# 05_3V3_GENERATION.net
KiCad netlist of a schematic drawn in Altium Designer
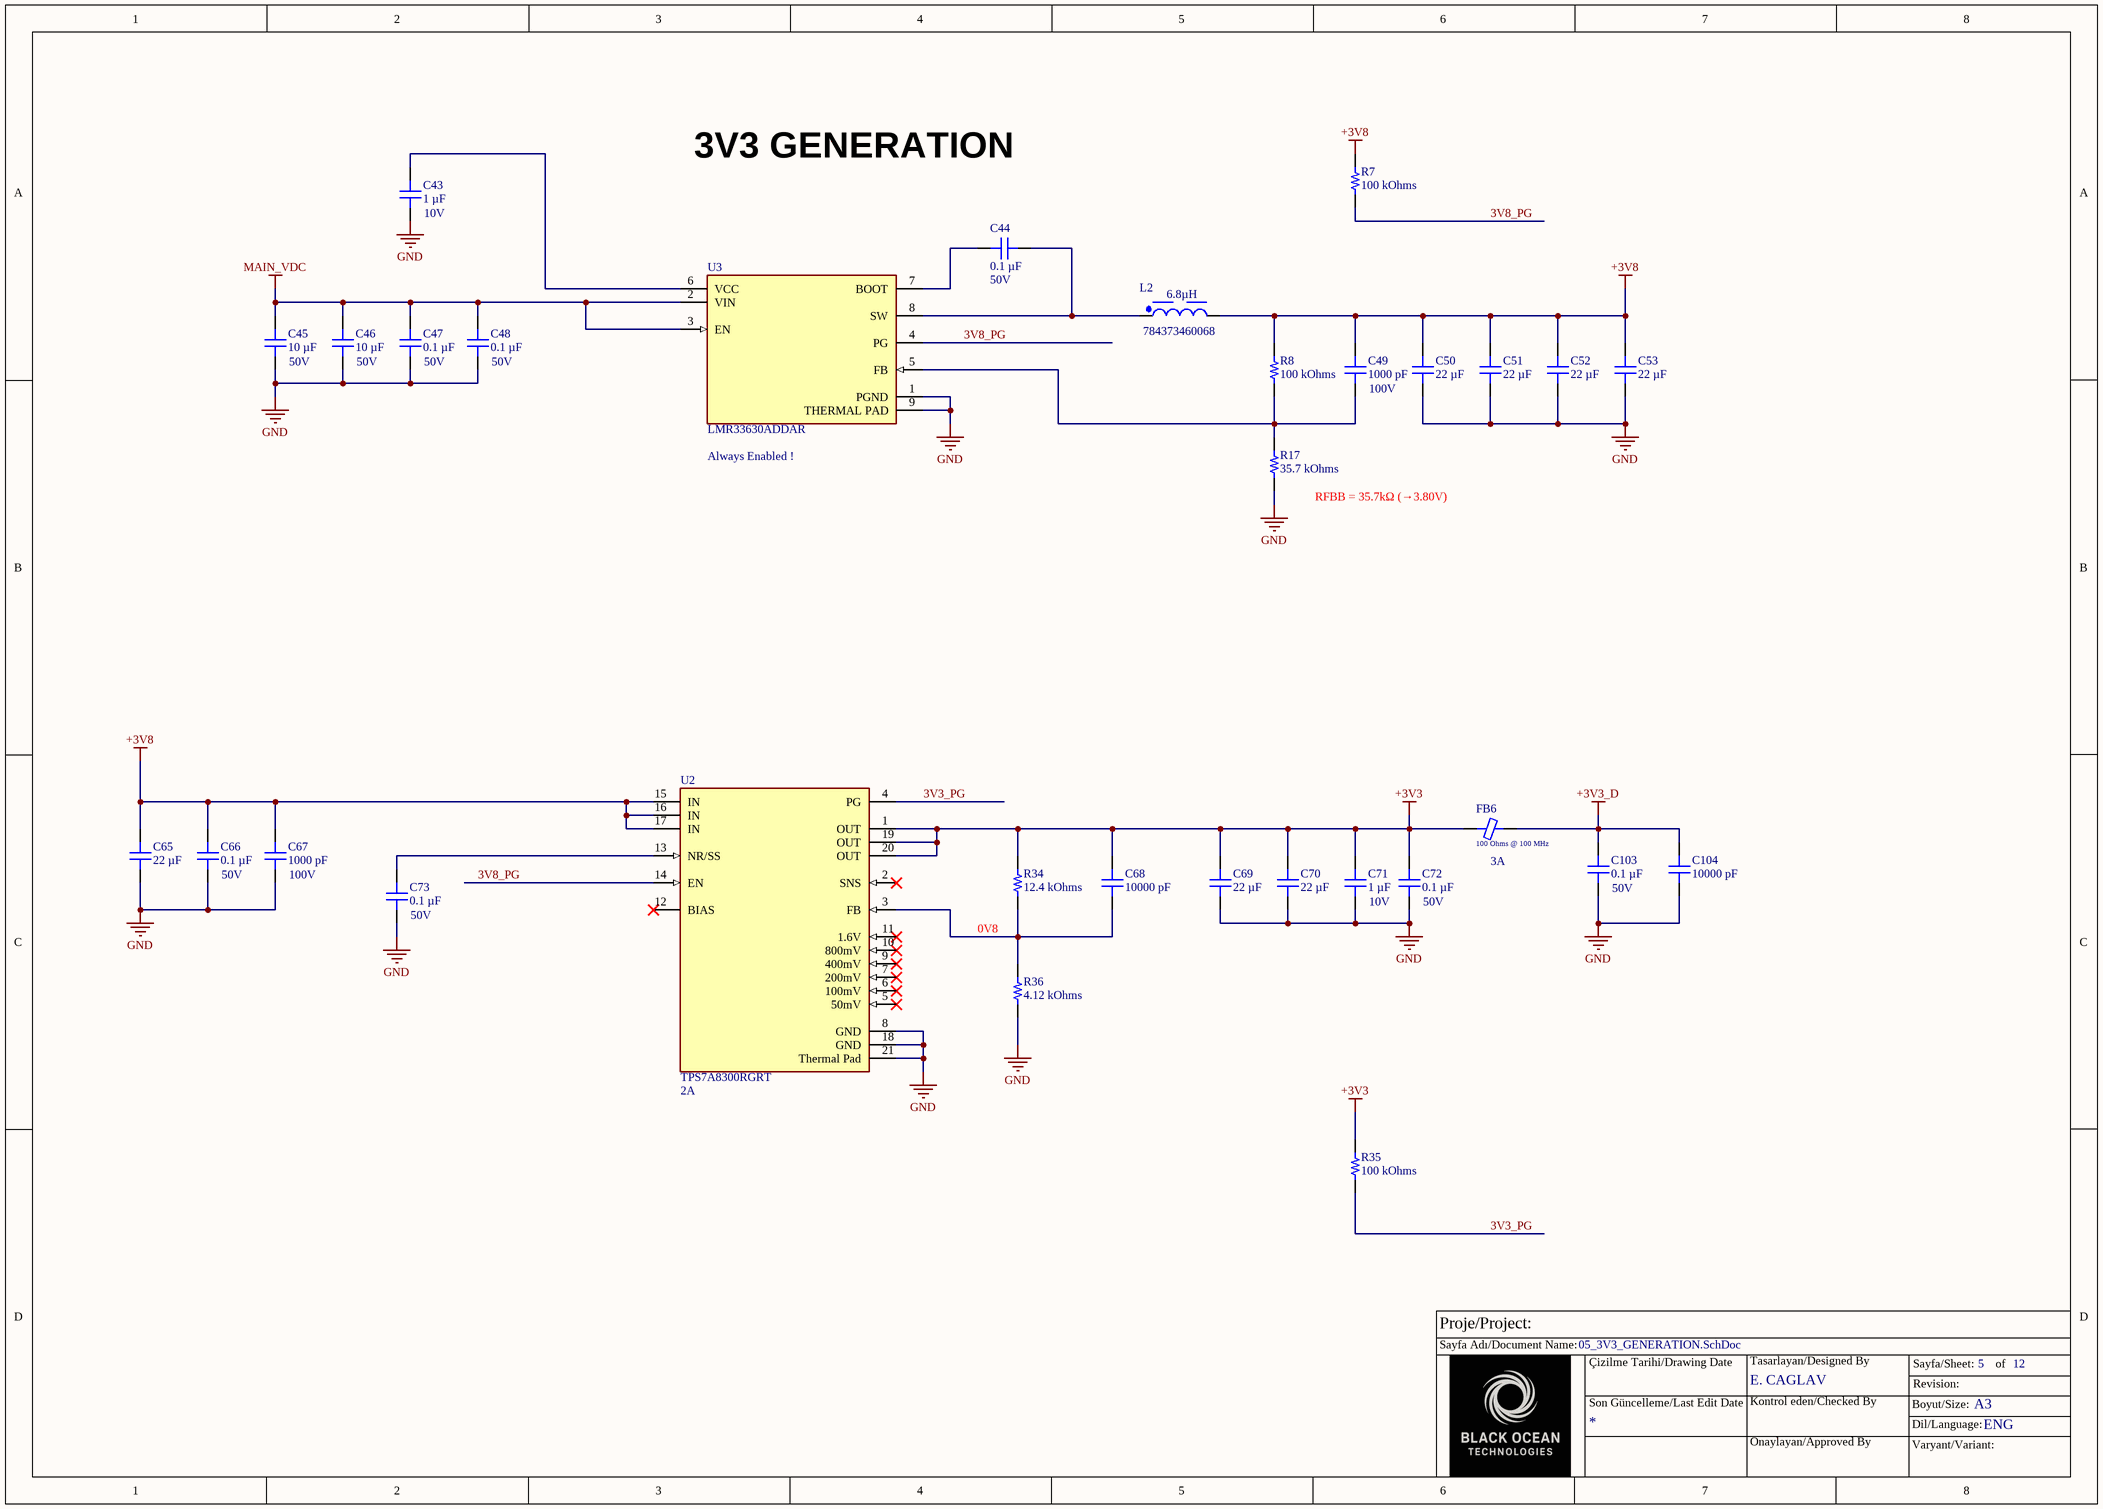
[diagram p0: 05_3V3_GENERATION.SchDoc]

(export (version "E")
  (design (tool "Eeschema 10.0.6"))
  (components
    (comp (ref "C43")
      (value "1 µF")
      (footprint "CAP 0402_1005")
      (description "CAP CER 1UF 10V X7S 0402")
      (fields
        (field (name "PART NUMBER") "GRM155C71A105KE11D")
        (field (name "CAPACITANCE") "1 µF")
        (field (name "MANUFACTURER") "Murata Electronics")
        (field (name "VOLTAGE - RATED") "10V")
      )
      (libsource (lib "Celestial Altium Library - altium_library") (part "Capacitor"))
    )
    (comp (ref "C44")
      (value "0.1 µF")
      (footprint "CAP 0402_1005")
      (description "CAP CER 0.1UF 50V X7R 0402")
      (fields
        (field (name "PART NUMBER") "GCM155R71H104KE02J")
        (field (name "CAPACITANCE") "0.1 µF")
        (field (name "MANUFACTURER") "Murata Electronics")
        (field (name "VOLTAGE - RATED") "50V")
      )
      (libsource (lib "Celestial Altium Library - altium_library") (part "Capacitor"))
    )
    (comp (ref "C45")
      (value "10 µF")
      (footprint "CAP 1206_3216 - 0.8MM")
      (description "CAP CER 10UF 50V X7R 1206")
      (fields
        (field (name "PART NUMBER") "CL31B106KBHNNNE")
        (field (name "CAPACITANCE") "10 µF")
        (field (name "MANUFACTURER") "Samsung Electro-Mechanics")
        (field (name "VOLTAGE - RATED") "50V")
      )
      (libsource (lib "Celestial Altium Library - altium_library") (part "Capacitor"))
    )
    (comp (ref "C46")
      (value "10 µF")
      (footprint "CAP 1206_3216 - 0.8MM")
      (description "CAP CER 10UF 50V X7R 1206")
      (fields
        (field (name "PART NUMBER") "CL31B106KBHNNNE")
        (field (name "CAPACITANCE") "10 µF")
        (field (name "MANUFACTURER") "Samsung Electro-Mechanics")
        (field (name "VOLTAGE - RATED") "50V")
      )
      (libsource (lib "Celestial Altium Library - altium_library") (part "Capacitor"))
    )
    (comp (ref "C47")
      (value "0.1 µF")
      (footprint "CAP 0402_1005")
      (description "CAP CER 0.1UF 50V X7R 0402")
      (fields
        (field (name "PART NUMBER") "GCM155R71H104KE02J")
        (field (name "CAPACITANCE") "0.1 µF")
        (field (name "MANUFACTURER") "Murata Electronics")
        (field (name "VOLTAGE - RATED") "50V")
      )
      (libsource (lib "Celestial Altium Library - altium_library") (part "Capacitor"))
    )
    (comp (ref "C48")
      (value "0.1 µF")
      (footprint "CAP 0402_1005")
      (description "CAP CER 0.1UF 50V X7R 0402")
      (fields
        (field (name "PART NUMBER") "GCM155R71H104KE02J")
        (field (name "CAPACITANCE") "0.1 µF")
        (field (name "MANUFACTURER") "Murata Electronics")
        (field (name "VOLTAGE - RATED") "50V")
      )
      (libsource (lib "Celestial Altium Library - altium_library") (part "Capacitor"))
    )
    (comp (ref "C49")
      (value "1000 pF")
      (footprint "CAP 0402_1005")
      (description "CAP CER 1000PF 100V C0G/NP0 0402")
      (fields
        (field (name "PART NUMBER") "C0402H102J1GAC7867")
        (field (name "CAPACITANCE") "1000 pF")
        (field (name "MANUFACTURER") "KEMET")
        (field (name "VOLTAGE - RATED") "100V")
      )
      (libsource (lib "Celestial Altium Library - altium_library") (part "Capacitor"))
    )
    (comp (ref "C50")
      (value "22 µF")
      (footprint "CAP 0805_2012")
      (description "CAP CER 22UF 16V X5R 0805")
      (fields
        (field (name "PART NUMBER") "CL21A226KOQNNNE")
        (field (name "CAPACITANCE") "22 µF")
        (field (name "MANUFACTURER") "Samsung Electro-Mechanics")
      )
      (libsource (lib "Celestial Altium Library - altium_library") (part "Capacitor"))
    )
    (comp (ref "C51")
      (value "22 µF")
      (footprint "CAP 0805_2012")
      (description "CAP CER 22UF 16V X5R 0805")
      (fields
        (field (name "PART NUMBER") "CL21A226KOQNNNE")
        (field (name "CAPACITANCE") "22 µF")
        (field (name "MANUFACTURER") "Samsung Electro-Mechanics")
      )
      (libsource (lib "Celestial Altium Library - altium_library") (part "Capacitor"))
    )
    (comp (ref "C52")
      (value "22 µF")
      (footprint "CAP 0805_2012")
      (description "CAP CER 22UF 16V X5R 0805")
      (fields
        (field (name "PART NUMBER") "CL21A226KOQNNNE")
        (field (name "CAPACITANCE") "22 µF")
        (field (name "MANUFACTURER") "Samsung Electro-Mechanics")
      )
      (libsource (lib "Celestial Altium Library - altium_library") (part "Capacitor"))
    )
    (comp (ref "C53")
      (value "22 µF")
      (footprint "CAP 0805_2012")
      (description "CAP CER 22UF 16V X5R 0805")
      (fields
        (field (name "PART NUMBER") "CL21A226KOQNNNE")
        (field (name "CAPACITANCE") "22 µF")
        (field (name "MANUFACTURER") "Samsung Electro-Mechanics")
      )
      (libsource (lib "Celestial Altium Library - altium_library") (part "Capacitor"))
    )
    (comp (ref "C65")
      (value "22 µF")
      (footprint "CAP 0805_2012")
      (description "CAP CER 22UF 16V X5R 0805")
      (fields
        (field (name "PART NUMBER") "CL21A226KOQNNNE")
        (field (name "CAPACITANCE") "22 µF")
        (field (name "MANUFACTURER") "Samsung Electro-Mechanics")
      )
      (libsource (lib "Celestial Altium Library - altium_library") (part "Capacitor"))
    )
    (comp (ref "C66")
      (value "0.1 µF")
      (footprint "CAP 0402_1005")
      (description "CAP CER 0.1UF 50V X7R 0402")
      (fields
        (field (name "PART NUMBER") "GCM155R71H104KE02J")
        (field (name "CAPACITANCE") "0.1 µF")
        (field (name "MANUFACTURER") "Murata Electronics")
        (field (name "VOLTAGE - RATED") "50V")
      )
      (libsource (lib "Celestial Altium Library - altium_library") (part "Capacitor"))
    )
    (comp (ref "C67")
      (value "1000 pF")
      (footprint "CAP 0402_1005")
      (description "CAP CER 1000PF 100V C0G/NP0 0402")
      (fields
        (field (name "PART NUMBER") "C0402H102J1GAC7867")
        (field (name "CAPACITANCE") "1000 pF")
        (field (name "MANUFACTURER") "KEMET")
        (field (name "VOLTAGE - RATED") "100V")
      )
      (libsource (lib "Celestial Altium Library - altium_library") (part "Capacitor"))
    )
    (comp (ref "C68")
      (value "10000 pF")
      (footprint "CAP 0402_1005")
      (description "CAP CER 10000PF 50V X7R 0402")
      (fields
        (field (name "PART NUMBER") "AC0402KPX7R9BB103")
        (field (name "CAPACITANCE") "10000 pF")
        (field (name "MANUFACTURER") "Yageo")
      )
      (libsource (lib "Celestial Altium Library - altium_library") (part "Capacitor"))
    )
    (comp (ref "C69")
      (value "22 µF")
      (footprint "CAP 0805_2012")
      (description "CAP CER 22UF 16V X5R 0805")
      (fields
        (field (name "PART NUMBER") "CL21A226KOQNNNE")
        (field (name "CAPACITANCE") "22 µF")
        (field (name "MANUFACTURER") "Samsung Electro-Mechanics")
      )
      (libsource (lib "Celestial Altium Library - altium_library") (part "Capacitor"))
    )
    (comp (ref "C70")
      (value "22 µF")
      (footprint "CAP 0805_2012")
      (description "CAP CER 22UF 16V X5R 0805")
      (fields
        (field (name "PART NUMBER") "CL21A226KOQNNNE")
        (field (name "CAPACITANCE") "22 µF")
        (field (name "MANUFACTURER") "Samsung Electro-Mechanics")
      )
      (libsource (lib "Celestial Altium Library - altium_library") (part "Capacitor"))
    )
    (comp (ref "C71")
      (value "1 µF")
      (footprint "CAP 0402_1005")
      (description "CAP CER 1UF 10V X7S 0402")
      (fields
        (field (name "PART NUMBER") "GRM155C71A105KE11D")
        (field (name "CAPACITANCE") "1 µF")
        (field (name "MANUFACTURER") "Murata Electronics")
        (field (name "VOLTAGE - RATED") "10V")
      )
      (libsource (lib "Celestial Altium Library - altium_library") (part "Capacitor"))
    )
    (comp (ref "C72")
      (value "0.1 µF")
      (footprint "CAP 0402_1005")
      (description "CAP CER 0.1UF 50V X7R 0402")
      (fields
        (field (name "PART NUMBER") "GCM155R71H104KE02J")
        (field (name "CAPACITANCE") "0.1 µF")
        (field (name "MANUFACTURER") "Murata Electronics")
        (field (name "VOLTAGE - RATED") "50V")
      )
      (libsource (lib "Celestial Altium Library - altium_library") (part "Capacitor"))
    )
    (comp (ref "C73")
      (value "0.1 µF")
      (footprint "CAP 0402_1005")
      (description "CAP CER 0.1UF 50V X7R 0402")
      (fields
        (field (name "PART NUMBER") "GCM155R71H104KE02J")
        (field (name "CAPACITANCE") "0.1 µF")
        (field (name "MANUFACTURER") "Murata Electronics")
        (field (name "VOLTAGE - RATED") "50V")
      )
      (libsource (lib "Celestial Altium Library - altium_library") (part "Capacitor"))
    )
    (comp (ref "C103")
      (value "0.1 µF")
      (footprint "CAP 0402_1005")
      (description "CAP CER 0.1UF 50V X7R 0402")
      (fields
        (field (name "PART NUMBER") "GCM155R71H104KE02J")
        (field (name "CAPACITANCE") "0.1 µF")
        (field (name "MANUFACTURER") "Murata Electronics")
        (field (name "VOLTAGE - RATED") "50V")
      )
      (libsource (lib "Celestial Altium Library - altium_library") (part "Capacitor"))
    )
    (comp (ref "C104")
      (value "10000 pF")
      (footprint "CAP 0402_1005")
      (description "CAP CER 10000PF 50V X7R 0402")
      (fields
        (field (name "PART NUMBER") "AC0402KPX7R9BB103")
        (field (name "CAPACITANCE") "10000 pF")
        (field (name "MANUFACTURER") "Yageo")
      )
      (libsource (lib "Celestial Altium Library - altium_library") (part "Capacitor"))
    )
    (comp (ref "FB6")
      (value "100 Ohms @ 100 MHz")
      (footprint "FER 0603_1608")
      (description "FERRITE BEAD 100 OHM 0603 1LN")
      (fields
        (field (name "PART NUMBER") "MH1608-101Y")
        (field (name "CURRENT RATING (MAX)") "3A")
        (field (name "MANUFACTURER") "Bourns Inc.")
      )
      (libsource (lib "Celestial Altium Library - altium_library") (part "Ferrite Chip"))
    )
    (comp (ref "L2")
      (value "784373460068")
      (footprint "WE-LHCA_7030")
      (description "Power Inductor, 6.8UH, 4.5A, Shielded Rohs Compliant: Yes")
      (fields (field (name "INDUCTANCE") "6.8µH"))
      (libsource (lib "Altium Content Vault") (part "Inductor - 2"))
    )
    (comp (ref "R7")
      (value "100 kOhms")
      (footprint "RES 0402_1005")
      (description "RES SMD 100K OHM 1% 1/16W 0402")
      (fields (field (name "PART NUMBER") "AC0402FR-07100KL") (field (name "MANUFACTURER") "Yageo"))
      (libsource (lib "Celestial Altium Library - altium_library") (part "Resistor"))
    )
    (comp (ref "R8")
      (value "100 kOhms")
      (footprint "RES 0402_1005")
      (description "RES 100K OHM 1% 1/16W 0402")
      (fields (field (name "PART NUMBER") "RC0402FR-13100KL") (field (name "MANUFACTURER") "Yageo"))
      (libsource (lib "Celestial Altium Library - altium_library") (part "Resistor"))
    )
    (comp (ref "R17")
      (value "35.7 kOhms")
      (footprint "RES 0402_1005")
      (description "RES SMD 35.7KOHM 0.1% 1/16W 0402")
      (fields
        (field (name "PART NUMBER") "ERA-2AEB3572X")
        (field (name "MANUFACTURER") "Panasonic Electronic Components")
      )
      (libsource (lib "Celestial Altium Library - altium_library") (part "Resistor"))
    )
    (comp (ref "R34")
      (value "12.4 kOhms")
      (footprint "RES 0402_1005")
      (description "RES SMD 12.4K OHM 1% 1/16W 0402")
      (fields (field (name "PART NUMBER") "AC0402FR-0712K4L") (field (name "MANUFACTURER") "Yageo"))
      (libsource (lib "Celestial Altium Library - altium_library") (part "Resistor"))
    )
    (comp (ref "R35")
      (value "100 kOhms")
      (footprint "RES 0402_1005")
      (description "RES SMD 100K OHM 1% 1/16W 0402")
      (fields (field (name "PART NUMBER") "AC0402FR-07100KL") (field (name "MANUFACTURER") "Yageo"))
      (libsource (lib "Celestial Altium Library - altium_library") (part "Resistor"))
    )
    (comp (ref "R36")
      (value "4.12 kOhms")
      (footprint "RES 0402_1005")
      (description "RES SMD 4.12KOHM 0.1% 1/16W 0402")
      (fields
        (field (name "PART NUMBER") "ERA-2AEB4121X")
        (field (name "MANUFACTURER") "Panasonic Electronic Components")
      )
      (libsource (lib "Celestial Altium Library - altium_library") (part "Resistor"))
    )
    (comp (ref "U2")
      (value "TPS7A8300RGRT")
      (footprint "FP-RGR0020A-MFG")
      (description "IC REG LINEAR POS ADJ 2A 20VQFN")
      (fields (field (name "OUTPUT CURRENT") "2A"))
      (libsource (lib "Altium Content Vault") (part "693c5293fa25e994f17fd2590bf4031"))
    )
    (comp (ref "U3")
      (value "LMR33630ADDAR")
      (footprint "FP-DDA0008J-MFG")
      (description "IC REG BUCK ADJUSTABLE 3A 8SOPWR")
      (libsource (lib "Altium Content Vault") (part "6a354f5098e7f60ae670b755afcc2ec"))
    )
  )
  (nets
    (net (code "1") (name "+3V3") (class "Default")
      (node (ref "C68") (pin "2") (pinfunction "2_2") (pintype "passive"))
      (node (ref "C69") (pin "2") (pinfunction "2_2") (pintype "passive"))
      (node (ref "C70") (pin "2") (pinfunction "2_2") (pintype "passive"))
      (node (ref "C71") (pin "1") (pinfunction "1_1") (pintype "passive"))
      (node (ref "C72") (pin "2") (pinfunction "2_2") (pintype "passive"))
      (node (ref "FB6") (pin "2") (pinfunction "2_2") (pintype "passive"))
      (node (ref "R34") (pin "2") (pinfunction "2_2") (pintype "passive"))
      (node (ref "R35") (pin "2") (pinfunction "2_2") (pintype "passive"))
      (node (ref "U2") (pin "1") (pinfunction "OUT_1") (pintype "passive"))
      (node (ref "U2") (pin "19") (pinfunction "OUT_19") (pintype "passive"))
      (node (ref "U2") (pin "20") (pinfunction "OUT_20") (pintype "passive"))
    )
    (net (code "2") (name "+3V3_D") (class "Default")
      (node (ref "C103") (pin "2") (pinfunction "2_2") (pintype "passive"))
      (node (ref "C104") (pin "2") (pinfunction "2_2") (pintype "passive"))
      (node (ref "FB6") (pin "1") (pinfunction "1_1") (pintype "passive"))
    )
    (net (code "3") (name "+3V8") (class "Default")
      (node (ref "C49") (pin "2") (pinfunction "2_2") (pintype "passive"))
      (node (ref "C50") (pin "2") (pinfunction "2_2") (pintype "passive"))
      (node (ref "C51") (pin "2") (pinfunction "2_2") (pintype "passive"))
      (node (ref "C52") (pin "2") (pinfunction "2_2") (pintype "passive"))
      (node (ref "C53") (pin "2") (pinfunction "2_2") (pintype "passive"))
      (node (ref "C65") (pin "2") (pinfunction "2_2") (pintype "passive"))
      (node (ref "C66") (pin "2") (pinfunction "2_2") (pintype "passive"))
      (node (ref "C67") (pin "2") (pinfunction "2_2") (pintype "passive"))
      (node (ref "L2") (pin "2") (pinfunction "2_2") (pintype "passive"))
      (node (ref "R7") (pin "2") (pinfunction "2_2") (pintype "passive"))
      (node (ref "R8") (pin "2") (pinfunction "2_2") (pintype "passive"))
      (node (ref "U2") (pin "15") (pinfunction "IN_15") (pintype "power_in"))
      (node (ref "U2") (pin "16") (pinfunction "IN_16") (pintype "power_in"))
      (node (ref "U2") (pin "17") (pinfunction "IN_17") (pintype "power_in"))
    )
    (net (code "4") (name "/3V3_PG") (class "Default")
      (node (ref "R35") (pin "1") (pinfunction "1_1") (pintype "passive"))
      (node (ref "U2") (pin "4") (pinfunction "PG_4") (pintype "open_collector"))
    )
    (net (code "5") (name "/3V8_PG") (class "Default")
      (node (ref "R7") (pin "1") (pinfunction "1_1") (pintype "passive"))
      (node (ref "U2") (pin "14") (pinfunction "EN_14") (pintype "input"))
      (node (ref "U3") (pin "4") (pinfunction "PG_4") (pintype "open_collector"))
    )
    (net (code "6") (name "GND") (class "Default")
      (node (ref "C103") (pin "1") (pinfunction "1_1") (pintype "passive"))
      (node (ref "C104") (pin "1") (pinfunction "1_1") (pintype "passive"))
      (node (ref "C43") (pin "2") (pinfunction "2_2") (pintype "passive"))
      (node (ref "C45") (pin "1") (pinfunction "1_1") (pintype "passive"))
      (node (ref "C46") (pin "1") (pinfunction "1_1") (pintype "passive"))
      (node (ref "C47") (pin "1") (pinfunction "1_1") (pintype "passive"))
      (node (ref "C48") (pin "1") (pinfunction "1_1") (pintype "passive"))
      (node (ref "C50") (pin "1") (pinfunction "1_1") (pintype "passive"))
      (node (ref "C51") (pin "1") (pinfunction "1_1") (pintype "passive"))
      (node (ref "C52") (pin "1") (pinfunction "1_1") (pintype "passive"))
      (node (ref "C53") (pin "1") (pinfunction "1_1") (pintype "passive"))
      (node (ref "C65") (pin "1") (pinfunction "1_1") (pintype "passive"))
      (node (ref "C66") (pin "1") (pinfunction "1_1") (pintype "passive"))
      (node (ref "C67") (pin "1") (pinfunction "1_1") (pintype "passive"))
      (node (ref "C69") (pin "1") (pinfunction "1_1") (pintype "passive"))
      (node (ref "C70") (pin "1") (pinfunction "1_1") (pintype "passive"))
      (node (ref "C71") (pin "2") (pinfunction "2_2") (pintype "passive"))
      (node (ref "C72") (pin "1") (pinfunction "1_1") (pintype "passive"))
      (node (ref "C73") (pin "1") (pinfunction "1_1") (pintype "passive"))
      (node (ref "R17") (pin "1") (pinfunction "1_1") (pintype "passive"))
      (node (ref "R36") (pin "1") (pinfunction "1_1") (pintype "passive"))
      (node (ref "U2") (pin "18") (pinfunction "GND_18") (pintype "power_in"))
      (node (ref "U2") (pin "21") (pinfunction "Thermal_Pad_21") (pintype "passive"))
      (node (ref "U2") (pin "8") (pinfunction "GND_8") (pintype "power_in"))
      (node (ref "U3") (pin "1") (pinfunction "PGND_1") (pintype "power_in"))
      (node (ref "U3") (pin "9") (pinfunction "THERMAL_PAD_9") (pintype "passive"))
    )
    (net (code "7") (name "MAIN_VDC") (class "Default")
      (node (ref "C45") (pin "2") (pinfunction "2_2") (pintype "passive"))
      (node (ref "C46") (pin "2") (pinfunction "2_2") (pintype "passive"))
      (node (ref "C47") (pin "2") (pinfunction "2_2") (pintype "passive"))
      (node (ref "C48") (pin "2") (pinfunction "2_2") (pintype "passive"))
      (node (ref "U3") (pin "2") (pinfunction "VIN_2") (pintype "power_in"))
      (node (ref "U3") (pin "3") (pinfunction "EN_3") (pintype "input"))
    )
    (net (code "8") (name "Net-(U2-FB)") (class "Default")
      (node (ref "C68") (pin "1") (pinfunction "1_1") (pintype "passive"))
      (node (ref "R34") (pin "1") (pinfunction "1_1") (pintype "passive"))
      (node (ref "R36") (pin "2") (pinfunction "2_2") (pintype "passive"))
      (node (ref "U2") (pin "3") (pinfunction "FB_3") (pintype "input"))
    )
    (net (code "9") (name "Net-(U2-NR{slash}SS)") (class "Default")
      (node (ref "C73") (pin "2") (pinfunction "2_2") (pintype "passive"))
      (node (ref "U2") (pin "13") (pinfunction "NR/SS_13") (pintype "input"))
    )
    (net (code "10") (name "Net-(U3-BOOT)") (class "Default")
      (node (ref "C44") (pin "2") (pinfunction "2_2") (pintype "passive"))
      (node (ref "U3") (pin "7") (pinfunction "BOOT_7") (pintype "passive"))
    )
    (net (code "11") (name "Net-(U3-FB)") (class "Default")
      (node (ref "C49") (pin "1") (pinfunction "1_1") (pintype "passive"))
      (node (ref "R17") (pin "2") (pinfunction "2_2") (pintype "passive"))
      (node (ref "R8") (pin "1") (pinfunction "1_1") (pintype "passive"))
      (node (ref "U3") (pin "5") (pinfunction "FB_5") (pintype "input"))
    )
    (net (code "12") (name "Net-(U3-SW)") (class "Default")
      (node (ref "C44") (pin "1") (pinfunction "1_1") (pintype "passive"))
      (node (ref "L2") (pin "1") (pinfunction "1_1") (pintype "passive"))
      (node (ref "U3") (pin "8") (pinfunction "SW_8") (pintype "passive"))
    )
    (net (code "13") (name "Net-(U3-VCC)") (class "Default")
      (node (ref "C43") (pin "1") (pinfunction "1_1") (pintype "passive"))
      (node (ref "U3") (pin "6") (pinfunction "VCC_6") (pintype "power_in"))
    )
    (net (code "14") (name "unconnected-(U2-1.6V-Pad11)") (class "Default")
      (node (ref "U2") (pin "11") (pinfunction "1.6V_11") (pintype "input+no_connect"))
    )
    (net (code "15") (name "unconnected-(U2-50mV-Pad5)") (class "Default")
      (node (ref "U2") (pin "5") (pinfunction "50mV_5") (pintype "input+no_connect"))
    )
    (net (code "16") (name "unconnected-(U2-100mV-Pad6)") (class "Default")
      (node (ref "U2") (pin "6") (pinfunction "100mV_6") (pintype "input+no_connect"))
    )
    (net (code "17") (name "unconnected-(U2-200mV-Pad7)") (class "Default")
      (node (ref "U2") (pin "7") (pinfunction "200mV_7") (pintype "input+no_connect"))
    )
    (net (code "18") (name "unconnected-(U2-400mV-Pad9)") (class "Default")
      (node (ref "U2") (pin "9") (pinfunction "400mV_9") (pintype "input+no_connect"))
    )
    (net (code "19") (name "unconnected-(U2-800mV-Pad10)") (class "Default")
      (node (ref "U2") (pin "10") (pinfunction "800mV_10") (pintype "input+no_connect"))
    )
    (net (code "20") (name "unconnected-(U2-BIAS-Pad12)") (class "Default")
      (node (ref "U2") (pin "12") (pinfunction "BIAS_12") (pintype "power_in+no_connect"))
    )
    (net (code "21") (name "unconnected-(U2-SNS-Pad2)") (class "Default")
      (node (ref "U2") (pin "2") (pinfunction "SNS_2") (pintype "input+no_connect"))
    )
  )
)
